# ACDC.net
KiCad netlist of a schematic drawn in Altium Designer
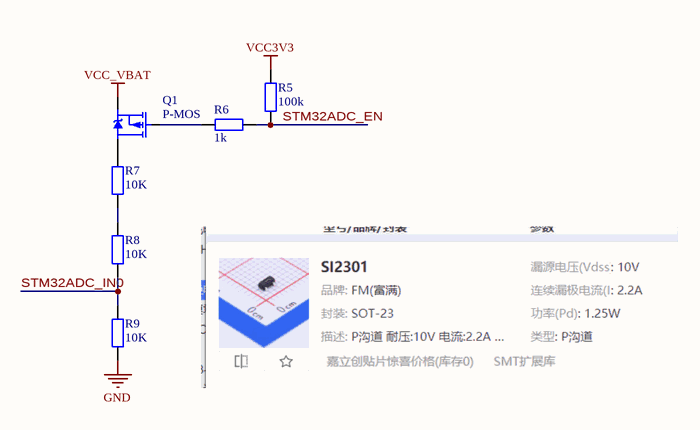
[diagram p0: ACDC.SchDoc]

(export (version "E")
  (design (tool "Eeschema 10.0.6"))
  (components
    (comp (ref "Q1")
      (value "P-MOS")
      (footprint "SOT23")
      (description "P沟道场效应管")
      (libsource (lib "STM32_Phone_2") (part "P-MOS"))
    )
    (comp (ref "R5")
      (value "100k")
      (footprint "R 0805_L")
      (description "贴片电阻")
      (fields (field (name "版权归属") "源创客"))
      (libsource (lib "STM32Project_1") (part "R_2"))
    )
    (comp (ref "R6")
      (value "1k")
      (footprint "R 0805_L")
      (description "贴片电阻")
      (fields (field (name "版权归属") "源创客"))
      (libsource (lib "STM32Project_1") (part "R_2"))
    )
    (comp (ref "R7")
      (value "10K")
      (footprint "R 0805_L")
      (description "贴片电阻")
      (fields (field (name "版权归属") "源创客"))
      (libsource (lib "STM32Project_1") (part "R_3"))
    )
    (comp (ref "R8")
      (value "10K")
      (footprint "R 0805_L")
      (description "贴片电阻")
      (fields (field (name "版权归属") "源创客"))
      (libsource (lib "STM32Project_1") (part "R_3"))
    )
    (comp (ref "R9")
      (value "10K")
      (footprint "R 0805_L")
      (description "贴片电阻")
      (fields (field (name "版权归属") "源创客"))
      (libsource (lib "STM32Project_1") (part "R_3"))
    )
  )
  (nets
    (net (code "1") (name "/STM32ADC_EN") (class "Default")
      (node (ref "R5") (pin "1") (pinfunction "1_1") (pintype "passive"))
      (node (ref "R6") (pin "1") (pinfunction "1_1") (pintype "passive"))
    )
    (net (code "2") (name "/STM32ADC_IN0") (class "Default")
      (node (ref "R8") (pin "1") (pinfunction "1_1") (pintype "passive"))
      (node (ref "R9") (pin "2") (pinfunction "2_2") (pintype "passive"))
    )
    (net (code "3") (name "GND") (class "Default")
      (node (ref "R9") (pin "1") (pinfunction "1_1") (pintype "passive"))
    )
    (net (code "4") (name "Net-(Q1-PadD)") (class "Default")
      (node (ref "Q1") (pin "D") (pinfunction "D_D") (pintype "passive"))
      (node (ref "R7") (pin "2") (pinfunction "2_2") (pintype "passive"))
    )
    (net (code "5") (name "Net-(Q1-PadG)") (class "Default")
      (node (ref "Q1") (pin "G") (pinfunction "G_G") (pintype "passive"))
      (node (ref "R6") (pin "2") (pinfunction "2_2") (pintype "passive"))
    )
    (net (code "6") (name "Net-(R7-Pad1)") (class "Default")
      (node (ref "R7") (pin "1") (pinfunction "1_1") (pintype "passive"))
      (node (ref "R8") (pin "2") (pinfunction "2_2") (pintype "passive"))
    )
    (net (code "7") (name "VCC3V3") (class "Default")
      (node (ref "R5") (pin "2") (pinfunction "2_2") (pintype "passive"))
    )
    (net (code "8") (name "VCC_VBAT") (class "Default")
      (node (ref "Q1") (pin "S") (pinfunction "S_S") (pintype "passive"))
    )
  )
)
